# apic.net
KiCad netlist of a schematic drawn in EAGLE
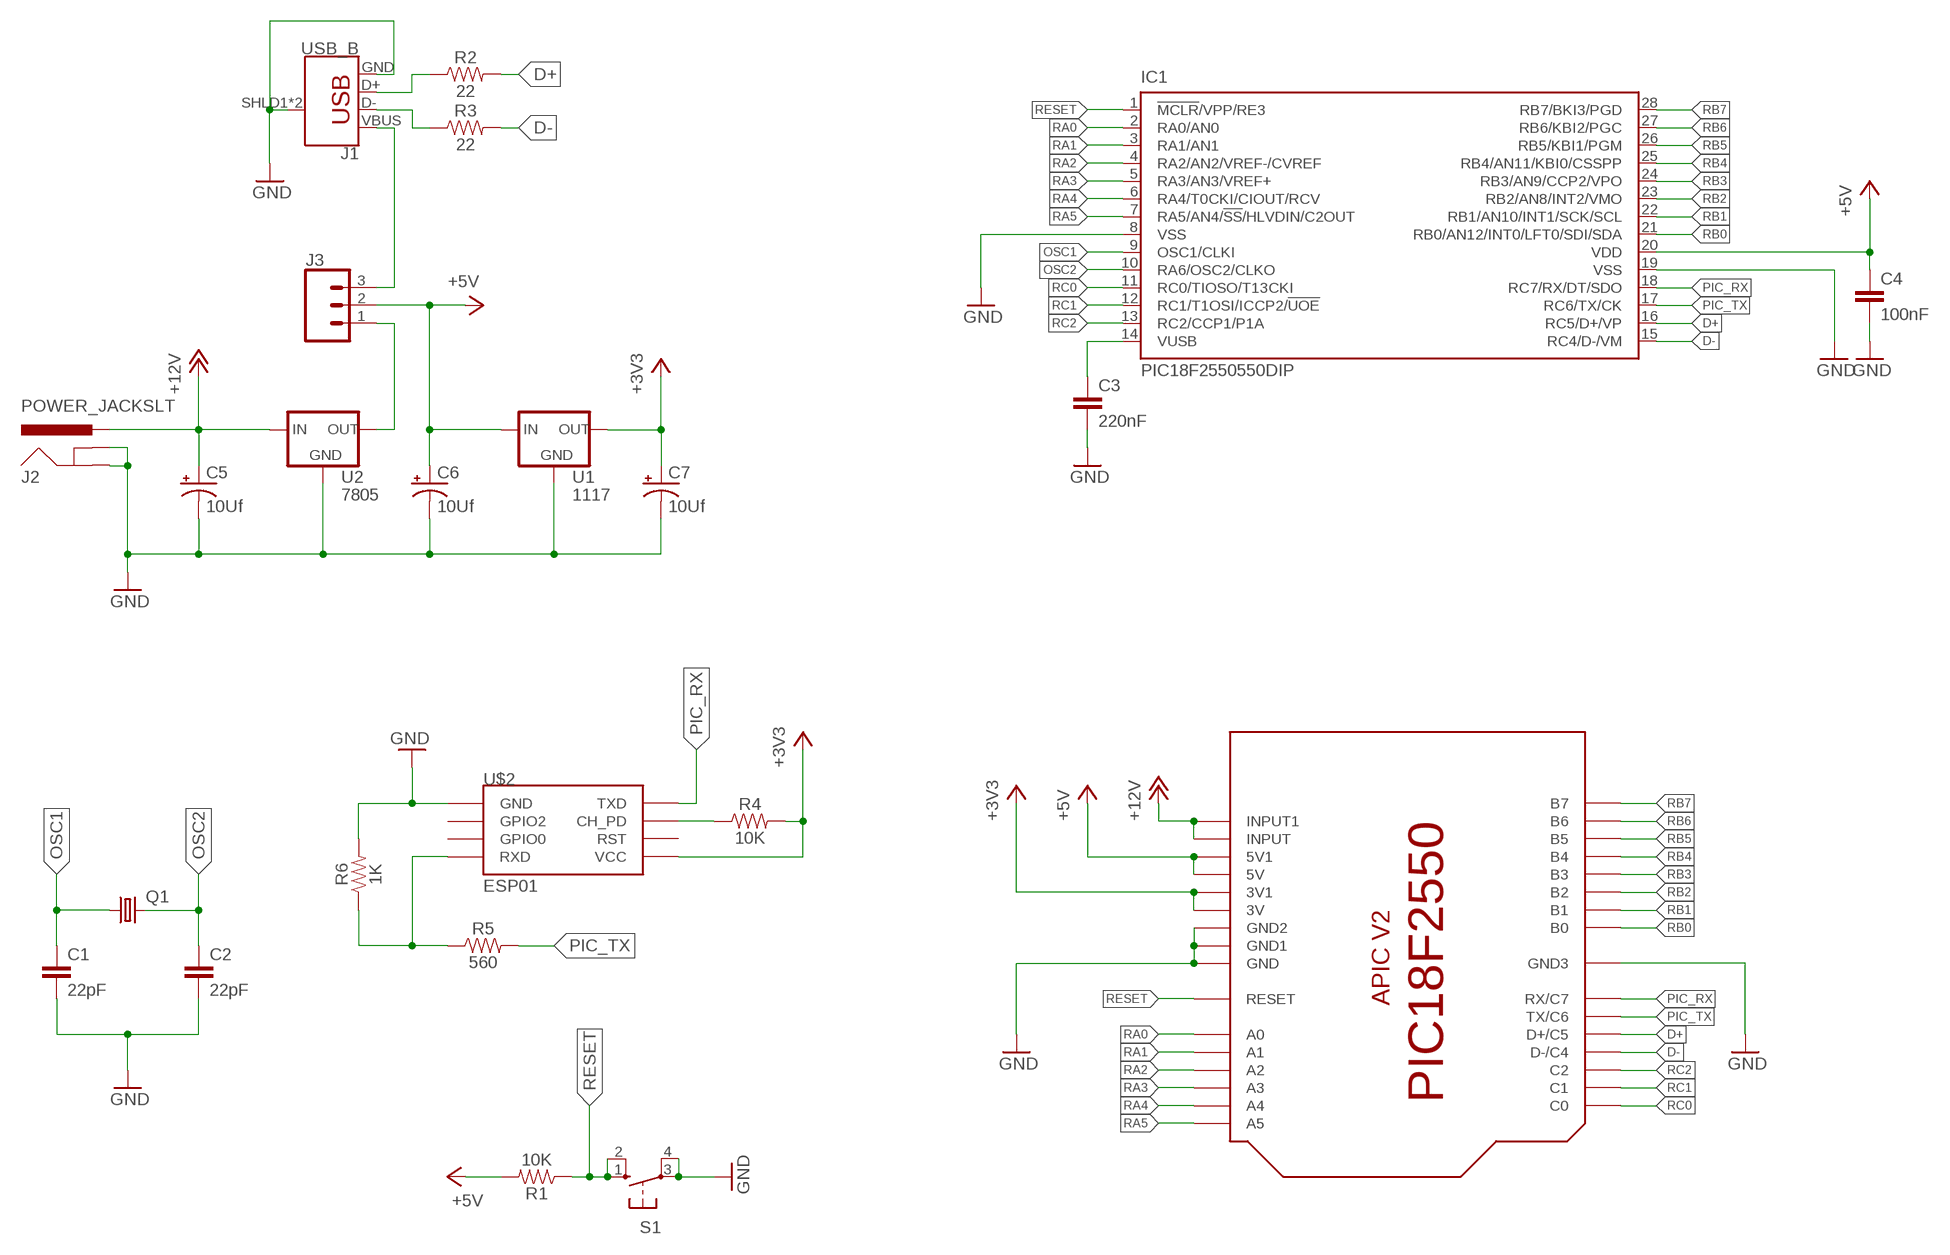
[diagram p0: schematic, sheet 1]

(export (version "E")
  (design (tool "Eeschema 10.0.6"))
  (components
    (comp (ref "C1")
      (value "22pF")
      (footprint "eagle-import:CAP-PTH-SMALL-KIT")
      (libsource (lib "eagle-import") (part "CAP-PTH-SMALL-KIT"))
    )
    (comp (ref "C2")
      (value "22pF")
      (footprint "eagle-import:CAP-PTH-SMALL-KIT")
      (libsource (lib "eagle-import") (part "CAP-PTH-SMALL-KIT"))
    )
    (comp (ref "C3")
      (value "220nF")
      (footprint "eagle-import:CAP-PTH-5MM")
      (libsource (lib "eagle-import") (part "CAP-PTH-5"))
    )
    (comp (ref "C4")
      (value "100nF")
      (footprint "eagle-import:CAP-PTH-SMALL-KIT")
      (libsource (lib "eagle-import") (part "CAP-PTH-SMALL-KIT"))
    )
    (comp (ref "C5")
      (value "10Uf")
      (footprint "eagle-import:CPOL-RADIAL-2.5MM-5MM")
      (libsource (lib "eagle-import") (part "CPOL-2.5-5"))
    )
    (comp (ref "C6")
      (value "10Uf")
      (footprint "eagle-import:CPOL-RADIAL-2.5MM-5MM")
      (libsource (lib "eagle-import") (part "CPOL-2.5-5"))
    )
    (comp (ref "C7")
      (value "10Uf")
      (footprint "eagle-import:CPOL-RADIAL-2.5MM-5MM")
      (libsource (lib "eagle-import") (part "CPOL-2.5-5"))
    )
    (comp (ref "IC1")
      (value "PIC18F2550550DIP")
      (footprint "eagle-import:SOCKET_DIL28")
      (fields (field (name "MF") "MICROCHIP") (field (name "MPN") "PIC18F2550-I/SP"))
      (libsource (lib "eagle-import") (part "PIC18F2550DIP550"))
    )
    (comp (ref "J1")
      (value "USB_B")
      (footprint "eagle-import:USB-B")
      (libsource (lib "eagle-import") (part "USB_B"))
    )
    (comp (ref "J2")
      (value "POWER_JACKSLT")
      (footprint "eagle-import:POWER_JACK")
      (libsource (lib "eagle-import") (part "POWER_JACKSLT"))
    )
    (comp (ref "J3")
      (value "CONN_03LONGPADS")
      (footprint "eagle-import:1X03_LONGPADS")
      (libsource (lib "eagle-import") (part "CONN_03LONGPADS"))
    )
    (comp (ref "Q1")
      (value "CRYSTAL")
      (footprint "eagle-import:CRYSTAL")
      (libsource (lib "eagle-import") (part "CRYSTAL"))
    )
    (comp (ref "R1")
      (value "10K")
      (footprint "eagle-import:AXIAL-0.3")
      (libsource (lib "eagle-import") (part "RESISTOR-AXIAL"))
    )
    (comp (ref "R2")
      (value "22")
      (footprint "eagle-import:AXIAL-0.3")
      (libsource (lib "eagle-import") (part "RESISTOR-AXIAL"))
    )
    (comp (ref "R3")
      (value "22")
      (footprint "eagle-import:AXIAL-0.3")
      (libsource (lib "eagle-import") (part "RESISTOR-AXIAL"))
    )
    (comp (ref "R4")
      (value "10K")
      (footprint "eagle-import:AXIAL-0.3")
      (libsource (lib "eagle-import") (part "RESISTOR-AXIAL"))
    )
    (comp (ref "R5")
      (value "560")
      (footprint "eagle-import:AXIAL-0.3")
      (libsource (lib "eagle-import") (part "RESISTOR-AXIAL"))
    )
    (comp (ref "R6")
      (value "1K")
      (footprint "eagle-import:AXIAL-0.3")
      (libsource (lib "eagle-import") (part "RESISTOR-AXIAL"))
    )
    (comp (ref "S1")
      (value "BUTTON")
      (footprint "eagle-import:BUTTON")
      (fields (field (name "MPN") "B3F-1000"))
      (libsource (lib "eagle-import") (part "BUTTON"))
    )
    (comp (ref "U$1")
      (value "APIC-18F2550")
      (footprint "eagle-import:APIC-18F2550")
      (libsource (lib "eagle-import") (part "APIC-18F2550"))
    )
    (comp (ref "U$2")
      (value "ESP01")
      (footprint "eagle-import:ESP01")
      (libsource (lib "eagle-import") (part "ESP01"))
    )
    (comp (ref "U1")
      (value "1117")
      (footprint "eagle-import:TO-220-ALT")
      (libsource (lib "eagle-import") (part "V_REG_1117-TO220ALT"))
    )
    (comp (ref "U2")
      (value "7805")
      (footprint "eagle-import:TO-220-ALT")
      (libsource (lib "eagle-import") (part "V_REG_7805-TO220ALT"))
    )
  )
  (nets
    (net (code "1") (name "+3V3") (class "Default")
      (node (ref "C7") (pin "+") (pinfunction "+_+") (pintype "passive"))
      (node (ref "R4") (pin "P$2") (pinfunction "2_P$2") (pintype "passive"))
      (node (ref "U$1") (pin "3V") (pinfunction "3V_3V") (pintype "power_in"))
      (node (ref "U$1") (pin "3V1") (pinfunction "3V1_3V1") (pintype "power_in"))
      (node (ref "U$2") (pin "VCC") (pinfunction "VCC_VCC") (pintype "bidirectional"))
      (node (ref "U1") (pin "2") (pinfunction "OUT_2") (pintype "passive"))
    )
    (net (code "2") (name "+5V") (class "Default")
      (node (ref "C4") (pin "1") (pinfunction "1_1") (pintype "passive"))
      (node (ref "C6") (pin "+") (pinfunction "+_+") (pintype "passive"))
      (node (ref "IC1") (pin "20") (pinfunction "VDD_20") (pintype "power_in"))
      (node (ref "J3") (pin "2") (pinfunction "2_2") (pintype "passive"))
      (node (ref "R1") (pin "P$2") (pinfunction "2_P$2") (pintype "passive"))
      (node (ref "U$1") (pin "5V") (pinfunction "5V_5V") (pintype "power_in"))
      (node (ref "U$1") (pin "5V1") (pinfunction "5V1_5V1") (pintype "power_in"))
      (node (ref "U1") (pin "3") (pinfunction "IN_3") (pintype "input"))
    )
    (net (code "3") (name "+12V") (class "Default")
      (node (ref "C5") (pin "+") (pinfunction "+_+") (pintype "passive"))
      (node (ref "J2") (pin "PWR") (pinfunction "PWR_PWR") (pintype "bidirectional"))
      (node (ref "U$1") (pin "INPUT") (pinfunction "INPUT_INPUT") (pintype "power_in"))
      (node (ref "U$1") (pin "INPUT1") (pinfunction "INPUT1_INPUT1") (pintype "power_in"))
      (node (ref "U2") (pin "1") (pinfunction "IN_1") (pintype "input"))
    )
    (net (code "4") (name "D+") (class "Default")
      (node (ref "IC1") (pin "16") (pinfunction "RC5/D+/VP_16") (pintype "bidirectional"))
      (node (ref "R2") (pin "P$2") (pinfunction "2_P$2") (pintype "passive"))
      (node (ref "U$1") (pin "C5") (pinfunction "D+/C5_C5") (pintype "bidirectional"))
    )
    (net (code "5") (name "D-") (class "Default")
      (node (ref "IC1") (pin "15") (pinfunction "RC4/D-/VM_15") (pintype "bidirectional"))
      (node (ref "R3") (pin "P$2") (pinfunction "2_P$2") (pintype "passive"))
      (node (ref "U$1") (pin "C4") (pinfunction "D-/C4_C4") (pintype "bidirectional"))
    )
    (net (code "6") (name "GND") (class "Default")
      (node (ref "C1") (pin "2") (pinfunction "2_2") (pintype "passive"))
      (node (ref "C2") (pin "2") (pinfunction "2_2") (pintype "passive"))
      (node (ref "C3") (pin "2") (pinfunction "2_2") (pintype "passive"))
      (node (ref "C4") (pin "2") (pinfunction "2_2") (pintype "passive"))
      (node (ref "C5") (pin "-") (pinfunction "-_-") (pintype "passive"))
      (node (ref "C6") (pin "-") (pinfunction "-_-") (pintype "passive"))
      (node (ref "C7") (pin "-") (pinfunction "-_-") (pintype "passive"))
      (node (ref "IC1") (pin "19") (pinfunction "VSS_19") (pintype "power_in"))
      (node (ref "IC1") (pin "8") (pinfunction "VSS_8") (pintype "power_in"))
      (node (ref "J1") (pin "GND") (pinfunction "GND_GND") (pintype "power_in"))
      (node (ref "J1") (pin "SHLD1") (pinfunction "SHIELD_SHLD1") (pintype "bidirectional"))
      (node (ref "J1") (pin "SHLD2") (pinfunction "SHIELD_SHLD2") (pintype "bidirectional"))
      (node (ref "J2") (pin "GND@1") (pinfunction "GNDBREAK_GND@1") (pintype "bidirectional"))
      (node (ref "J2") (pin "GND@2") (pinfunction "GND_GND@2") (pintype "bidirectional"))
      (node (ref "R6") (pin "P$2") (pinfunction "2_P$2") (pintype "passive"))
      (node (ref "S1") (pin "3") (pinfunction "P_3") (pintype "passive"))
      (node (ref "S1") (pin "4") (pinfunction "P1_4") (pintype "passive"))
      (node (ref "U$1") (pin "GND") (pinfunction "GND_GND") (pintype "power_in"))
      (node (ref "U$1") (pin "GND1") (pinfunction "GND1_GND1") (pintype "power_in"))
      (node (ref "U$1") (pin "GND2") (pinfunction "GND2_GND2") (pintype "power_in"))
      (node (ref "U$1") (pin "GND3") (pinfunction "GND3_GND3") (pintype "power_in"))
      (node (ref "U$2") (pin "GND") (pinfunction "GND_GND") (pintype "bidirectional"))
      (node (ref "U1") (pin "1") (pinfunction "GND_1") (pintype "input"))
      (node (ref "U2") (pin "2") (pinfunction "GND_2") (pintype "input"))
    )
    (net (code "7") (name "Net-(IC1-VUSB)") (class "Default")
      (node (ref "C3") (pin "1") (pinfunction "1_1") (pintype "passive"))
      (node (ref "IC1") (pin "14") (pinfunction "VUSB_14") (pintype "bidirectional"))
    )
    (net (code "8") (name "Net-(J1-PadVBUS)") (class "Default")
      (node (ref "J1") (pin "VBUS") (pinfunction "VBUS_VBUS") (pintype "power_in"))
      (node (ref "J3") (pin "3") (pinfunction "3_3") (pintype "passive"))
    )
    (net (code "9") (name "Net-(R2-1)") (class "Default")
      (node (ref "J1") (pin "D+") (pinfunction "D+_D+") (pintype "bidirectional"))
      (node (ref "R2") (pin "P$1") (pinfunction "1_P$1") (pintype "passive"))
    )
    (net (code "10") (name "Net-(R3-1)") (class "Default")
      (node (ref "J1") (pin "D-") (pinfunction "D-_D-") (pintype "bidirectional"))
      (node (ref "R3") (pin "P$1") (pinfunction "1_P$1") (pintype "passive"))
    )
    (net (code "11") (name "Net-(R4-1)") (class "Default")
      (node (ref "R4") (pin "P$1") (pinfunction "1_P$1") (pintype "passive"))
      (node (ref "U$2") (pin "CH_PD") (pinfunction "CH_PD_CH_PD") (pintype "bidirectional"))
    )
    (net (code "12") (name "Net-(R5-1)") (class "Default")
      (node (ref "R5") (pin "P$1") (pinfunction "1_P$1") (pintype "passive"))
      (node (ref "R6") (pin "P$1") (pinfunction "1_P$1") (pintype "passive"))
      (node (ref "U$2") (pin "RX") (pinfunction "RXD_RX") (pintype "bidirectional"))
    )
    (net (code "13") (name "Net-(U2-OUT)") (class "Default")
      (node (ref "J3") (pin "1") (pinfunction "1_1") (pintype "passive"))
      (node (ref "U2") (pin "3") (pinfunction "OUT_3") (pintype "passive"))
    )
    (net (code "14") (name "OSC1") (class "Default")
      (node (ref "C1") (pin "1") (pinfunction "1_1") (pintype "passive"))
      (node (ref "IC1") (pin "9") (pinfunction "OSC1/CLKI_9") (pintype "input"))
      (node (ref "Q1") (pin "1") (pinfunction "1_1") (pintype "passive"))
    )
    (net (code "15") (name "OSC2") (class "Default")
      (node (ref "C2") (pin "1") (pinfunction "1_1") (pintype "passive"))
      (node (ref "IC1") (pin "10") (pinfunction "RA6/OSC2/CLKO_10") (pintype "output"))
      (node (ref "Q1") (pin "2") (pinfunction "2_2") (pintype "passive"))
    )
    (net (code "16") (name "PIC_RX") (class "Default")
      (node (ref "IC1") (pin "18") (pinfunction "RC7/RX/DT/SDO_18") (pintype "bidirectional"))
      (node (ref "U$1") (pin "C7") (pinfunction "RX/C7_C7") (pintype "bidirectional"))
      (node (ref "U$2") (pin "TX") (pinfunction "TXD_TX") (pintype "bidirectional"))
    )
    (net (code "17") (name "PIC_TX") (class "Default")
      (node (ref "IC1") (pin "17") (pinfunction "RC6/TX/CK_17") (pintype "bidirectional"))
      (node (ref "R5") (pin "P$2") (pinfunction "2_P$2") (pintype "passive"))
      (node (ref "U$1") (pin "C6") (pinfunction "TX/C6_C6") (pintype "bidirectional"))
    )
    (net (code "18") (name "RA0") (class "Default")
      (node (ref "IC1") (pin "2") (pinfunction "RA0/AN0_2") (pintype "bidirectional"))
      (node (ref "U$1") (pin "A0") (pinfunction "A0_A0") (pintype "bidirectional"))
    )
    (net (code "19") (name "RA1") (class "Default")
      (node (ref "IC1") (pin "3") (pinfunction "RA1/AN1_3") (pintype "bidirectional"))
      (node (ref "U$1") (pin "A1") (pinfunction "A1_A1") (pintype "bidirectional"))
    )
    (net (code "20") (name "RA2") (class "Default")
      (node (ref "IC1") (pin "4") (pinfunction "RA2/AN2/VREF-/CVREF_4") (pintype "bidirectional"))
      (node (ref "U$1") (pin "A2") (pinfunction "A2_A2") (pintype "bidirectional"))
    )
    (net (code "21") (name "RA3") (class "Default")
      (node (ref "IC1") (pin "5") (pinfunction "RA3/AN3/VREF+_5") (pintype "bidirectional"))
      (node (ref "U$1") (pin "A3") (pinfunction "A3_A3") (pintype "bidirectional"))
    )
    (net (code "22") (name "RA4") (class "Default")
      (node (ref "IC1") (pin "6") (pinfunction "RA4/T0CKI/CIOUT/RCV_6") (pintype "bidirectional"))
      (node (ref "U$1") (pin "A4") (pinfunction "A4_A4") (pintype "bidirectional"))
    )
    (net (code "23") (name "RA5") (class "Default")
      (node (ref "IC1") (pin "7") (pinfunction "RA5/AN4/~{SS}/HLVDIN/C2OUT_7") (pintype "bidirectional"))
      (node (ref "U$1") (pin "A5") (pinfunction "A5_A5") (pintype "bidirectional"))
    )
    (net (code "24") (name "RB0") (class "Default")
      (node (ref "IC1") (pin "21") (pinfunction "RB0/AN12/INT0/LFT0/SDI/SDA_21") (pintype "bidirectional"))
      (node (ref "U$1") (pin "B0") (pinfunction "B0_B0") (pintype "bidirectional"))
    )
    (net (code "25") (name "RB1") (class "Default")
      (node (ref "IC1") (pin "22") (pinfunction "RB1/AN10/INT1/SCK/SCL_22") (pintype "bidirectional"))
      (node (ref "U$1") (pin "B1") (pinfunction "B1_B1") (pintype "bidirectional"))
    )
    (net (code "26") (name "RB2") (class "Default")
      (node (ref "IC1") (pin "23") (pinfunction "RB2/AN8/INT2/VMO_23") (pintype "bidirectional"))
      (node (ref "U$1") (pin "B2") (pinfunction "B2_B2") (pintype "bidirectional"))
    )
    (net (code "27") (name "RB3") (class "Default")
      (node (ref "IC1") (pin "24") (pinfunction "RB3/AN9/CCP2/VPO_24") (pintype "bidirectional"))
      (node (ref "U$1") (pin "B3") (pinfunction "B3_B3") (pintype "bidirectional"))
    )
    (net (code "28") (name "RB4") (class "Default")
      (node (ref "IC1") (pin "25") (pinfunction "RB4/AN11/KBI0/CSSPP_25") (pintype "bidirectional"))
      (node (ref "U$1") (pin "B4") (pinfunction "B4_B4") (pintype "bidirectional"))
    )
    (net (code "29") (name "RB5") (class "Default")
      (node (ref "IC1") (pin "26") (pinfunction "RB5/KBI1/PGM_26") (pintype "bidirectional"))
      (node (ref "U$1") (pin "B5") (pinfunction "B5_B5") (pintype "bidirectional"))
    )
    (net (code "30") (name "RB6") (class "Default")
      (node (ref "IC1") (pin "27") (pinfunction "RB6/KBI2/PGC_27") (pintype "bidirectional"))
      (node (ref "U$1") (pin "B6") (pinfunction "B6_B6") (pintype "bidirectional"))
    )
    (net (code "31") (name "RB7") (class "Default")
      (node (ref "IC1") (pin "28") (pinfunction "RB7/BKI3/PGD_28") (pintype "bidirectional"))
      (node (ref "U$1") (pin "B7") (pinfunction "B7_B7") (pintype "bidirectional"))
    )
    (net (code "32") (name "RC0") (class "Default")
      (node (ref "IC1") (pin "11") (pinfunction "RC0/TIOSO/T13CKI_11") (pintype "bidirectional"))
      (node (ref "U$1") (pin "C0") (pinfunction "C0_C0") (pintype "bidirectional"))
    )
    (net (code "33") (name "RC1") (class "Default")
      (node (ref "IC1") (pin "12") (pinfunction "RC1/T1OSI/ICCP2/~{UOE}_12") (pintype "bidirectional"))
      (node (ref "U$1") (pin "C1") (pinfunction "C1_C1") (pintype "bidirectional"))
    )
    (net (code "34") (name "RC2") (class "Default")
      (node (ref "IC1") (pin "13") (pinfunction "RC2/CCP1/P1A_13") (pintype "bidirectional"))
      (node (ref "U$1") (pin "C2") (pinfunction "C2_C2") (pintype "bidirectional"))
    )
    (net (code "35") (name "RESET") (class "Default")
      (node (ref "IC1") (pin "1") (pinfunction "~{MCLR}/VPP/RE3_1") (pintype "input"))
      (node (ref "R1") (pin "P$1") (pinfunction "1_P$1") (pintype "passive"))
      (node (ref "S1") (pin "1") (pinfunction "S_1") (pintype "passive"))
      (node (ref "S1") (pin "2") (pinfunction "S1_2") (pintype "passive"))
      (node (ref "U$1") (pin "RESET") (pinfunction "RESET_RESET") (pintype "bidirectional"))
    )
    (net (code "36") (name "unconnected-(U$2-PadGPIO0)") (class "Default")
      (node (ref "U$2") (pin "GPIO0") (pinfunction "GPIO0_GPIO0") (pintype "bidirectional"))
    )
    (net (code "37") (name "unconnected-(U$2-PadGPIO2)") (class "Default")
      (node (ref "U$2") (pin "GPIO2") (pinfunction "GPIO2_GPIO2") (pintype "bidirectional"))
    )
    (net (code "38") (name "unconnected-(U$2-PadRST)") (class "Default")
      (node (ref "U$2") (pin "RST") (pinfunction "RST_RST") (pintype "bidirectional"))
    )
  )
)
